# mem.net
KiCad netlist of a schematic drawn in EAGLE
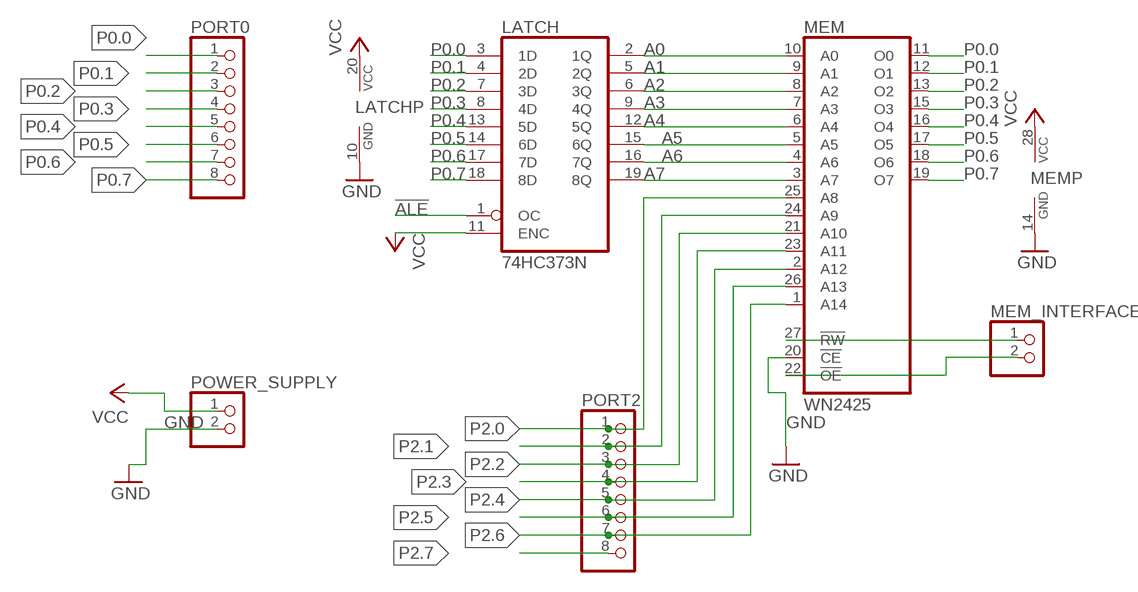
[diagram p0: schematic, sheet 1]

(export (version "E")
  (design (tool "Eeschema 10.0.6"))
  (components
    (comp (ref "LATCH")
      (value "74HC373N")
      (footprint "eagle-import:DIL20")
      (libsource (lib "eagle-import") (part "74373NHC"))
    )
    (comp (ref "MEM")
      (value "WN2425")
      (footprint "eagle-import:DIL28")
      (libsource (lib "eagle-import") (part "TC55257DP"))
    )
    (comp (ref "MEM_INTERFACE")
      (value "PINHD-1X2")
      (footprint "eagle-import:1X02")
      (libsource (lib "eagle-import") (part "PINHD-1X2"))
    )
    (comp (ref "PORT0")
      (value "PINHD-1X8")
      (footprint "eagle-import:1X08")
      (libsource (lib "eagle-import") (part "PINHD-1X8"))
    )
    (comp (ref "PORT2")
      (value "PINHD-1X8")
      (footprint "eagle-import:1X08")
      (libsource (lib "eagle-import") (part "PINHD-1X8"))
    )
    (comp (ref "POWER_SUPPLY")
      (value "PINHD-1X2")
      (footprint "eagle-import:1X02")
      (libsource (lib "eagle-import") (part "PINHD-1X2"))
    )
  )
  (nets
    (net (code "1") (name "/A0") (class "Default")
      (node (ref "LATCH") (pin "2") (pinfunction "1Q_2") (pintype "tri_state"))
      (node (ref "MEM") (pin "10") (pinfunction "A0_10") (pintype "input"))
    )
    (net (code "2") (name "/A1") (class "Default")
      (node (ref "LATCH") (pin "5") (pinfunction "2Q_5") (pintype "tri_state"))
      (node (ref "MEM") (pin "9") (pinfunction "A1_9") (pintype "input"))
    )
    (net (code "3") (name "/A2") (class "Default")
      (node (ref "LATCH") (pin "6") (pinfunction "3Q_6") (pintype "tri_state"))
      (node (ref "MEM") (pin "8") (pinfunction "A2_8") (pintype "input"))
    )
    (net (code "4") (name "/A3") (class "Default")
      (node (ref "LATCH") (pin "9") (pinfunction "4Q_9") (pintype "tri_state"))
      (node (ref "MEM") (pin "7") (pinfunction "A3_7") (pintype "input"))
    )
    (net (code "5") (name "/A4") (class "Default")
      (node (ref "LATCH") (pin "12") (pinfunction "5Q_12") (pintype "tri_state"))
      (node (ref "MEM") (pin "6") (pinfunction "A4_6") (pintype "input"))
    )
    (net (code "6") (name "/A5") (class "Default")
      (node (ref "LATCH") (pin "15") (pinfunction "6Q_15") (pintype "tri_state"))
      (node (ref "MEM") (pin "5") (pinfunction "A5_5") (pintype "input"))
    )
    (net (code "7") (name "/A6") (class "Default")
      (node (ref "LATCH") (pin "16") (pinfunction "7Q_16") (pintype "tri_state"))
      (node (ref "MEM") (pin "4") (pinfunction "A6_4") (pintype "input"))
    )
    (net (code "8") (name "/A7") (class "Default")
      (node (ref "LATCH") (pin "19") (pinfunction "8Q_19") (pintype "tri_state"))
      (node (ref "MEM") (pin "3") (pinfunction "A7_3") (pintype "input"))
    )
    (net (code "9") (name "/~{ALE}") (class "Default")
      (node (ref "LATCH") (pin "1") (pinfunction "OC_1") (pintype "input"))
    )
    (net (code "10") (name "GND") (class "Default")
      (node (ref "LATCH") (pin "10") (pinfunction "GND_10") (pintype "power_in"))
      (node (ref "MEM") (pin "14") (pinfunction "GND_14") (pintype "power_in"))
      (node (ref "MEM") (pin "20") (pinfunction "~{CE}_20") (pintype "input"))
      (node (ref "POWER_SUPPLY") (pin "2") (pinfunction "2_2") (pintype "passive"))
    )
    (net (code "11") (name "Net-(MEMA-~{OE})") (class "Default")
      (node (ref "MEM") (pin "22") (pinfunction "~{OE}_22") (pintype "input"))
      (node (ref "MEM_INTERFACE") (pin "2") (pinfunction "2_2") (pintype "passive"))
    )
    (net (code "12") (name "Net-(MEMA-~{RW})") (class "Default")
      (node (ref "MEM") (pin "27") (pinfunction "~{RW}_27") (pintype "input"))
      (node (ref "MEM_INTERFACE") (pin "1") (pinfunction "1_1") (pintype "passive"))
    )
    (net (code "13") (name "P0.0") (class "Default")
      (node (ref "LATCH") (pin "3") (pinfunction "1D_3") (pintype "input"))
      (node (ref "MEM") (pin "11") (pinfunction "O0_11") (pintype "tri_state"))
      (node (ref "PORT0") (pin "1") (pinfunction "1_1") (pintype "passive"))
    )
    (net (code "14") (name "P0.1") (class "Default")
      (node (ref "LATCH") (pin "4") (pinfunction "2D_4") (pintype "input"))
      (node (ref "MEM") (pin "12") (pinfunction "O1_12") (pintype "tri_state"))
      (node (ref "PORT0") (pin "2") (pinfunction "2_2") (pintype "passive"))
    )
    (net (code "15") (name "P0.2") (class "Default")
      (node (ref "LATCH") (pin "7") (pinfunction "3D_7") (pintype "input"))
      (node (ref "MEM") (pin "13") (pinfunction "O2_13") (pintype "tri_state"))
      (node (ref "PORT0") (pin "3") (pinfunction "3_3") (pintype "passive"))
    )
    (net (code "16") (name "P0.3") (class "Default")
      (node (ref "LATCH") (pin "8") (pinfunction "4D_8") (pintype "input"))
      (node (ref "MEM") (pin "15") (pinfunction "O3_15") (pintype "tri_state"))
      (node (ref "PORT0") (pin "4") (pinfunction "4_4") (pintype "passive"))
    )
    (net (code "17") (name "P0.4") (class "Default")
      (node (ref "LATCH") (pin "13") (pinfunction "5D_13") (pintype "input"))
      (node (ref "MEM") (pin "16") (pinfunction "O4_16") (pintype "tri_state"))
      (node (ref "PORT0") (pin "5") (pinfunction "5_5") (pintype "passive"))
    )
    (net (code "18") (name "P0.5") (class "Default")
      (node (ref "LATCH") (pin "14") (pinfunction "6D_14") (pintype "input"))
      (node (ref "MEM") (pin "17") (pinfunction "O5_17") (pintype "tri_state"))
      (node (ref "PORT0") (pin "6") (pinfunction "6_6") (pintype "passive"))
    )
    (net (code "19") (name "P0.6") (class "Default")
      (node (ref "LATCH") (pin "17") (pinfunction "7D_17") (pintype "input"))
      (node (ref "MEM") (pin "18") (pinfunction "O6_18") (pintype "tri_state"))
      (node (ref "PORT0") (pin "7") (pinfunction "7_7") (pintype "passive"))
    )
    (net (code "20") (name "P0.7") (class "Default")
      (node (ref "LATCH") (pin "18") (pinfunction "8D_18") (pintype "input"))
      (node (ref "MEM") (pin "19") (pinfunction "O7_19") (pintype "tri_state"))
      (node (ref "PORT0") (pin "8") (pinfunction "8_8") (pintype "passive"))
    )
    (net (code "21") (name "P2.0") (class "Default")
      (node (ref "MEM") (pin "25") (pinfunction "A8_25") (pintype "input"))
      (node (ref "PORT2") (pin "1") (pinfunction "1_1") (pintype "passive"))
    )
    (net (code "22") (name "P2.1") (class "Default")
      (node (ref "MEM") (pin "24") (pinfunction "A9_24") (pintype "input"))
      (node (ref "PORT2") (pin "2") (pinfunction "2_2") (pintype "passive"))
    )
    (net (code "23") (name "P2.2") (class "Default")
      (node (ref "MEM") (pin "21") (pinfunction "A10_21") (pintype "input"))
      (node (ref "PORT2") (pin "3") (pinfunction "3_3") (pintype "passive"))
    )
    (net (code "24") (name "P2.3") (class "Default")
      (node (ref "MEM") (pin "23") (pinfunction "A11_23") (pintype "input"))
      (node (ref "PORT2") (pin "4") (pinfunction "4_4") (pintype "passive"))
    )
    (net (code "25") (name "P2.4") (class "Default")
      (node (ref "MEM") (pin "2") (pinfunction "A12_2") (pintype "input"))
      (node (ref "PORT2") (pin "5") (pinfunction "5_5") (pintype "passive"))
    )
    (net (code "26") (name "P2.5") (class "Default")
      (node (ref "MEM") (pin "26") (pinfunction "A13_26") (pintype "input"))
      (node (ref "PORT2") (pin "6") (pinfunction "6_6") (pintype "passive"))
    )
    (net (code "27") (name "P2.6") (class "Default")
      (node (ref "MEM") (pin "1") (pinfunction "A14_1") (pintype "input"))
      (node (ref "PORT2") (pin "7") (pinfunction "7_7") (pintype "passive"))
    )
    (net (code "28") (name "P2.7") (class "Default")
      (node (ref "PORT2") (pin "8") (pinfunction "8_8") (pintype "passive"))
    )
    (net (code "29") (name "VCC") (class "Default")
      (node (ref "LATCH") (pin "11") (pinfunction "ENC_11") (pintype "input"))
      (node (ref "LATCH") (pin "20") (pinfunction "VCC_20") (pintype "power_in"))
      (node (ref "MEM") (pin "28") (pinfunction "VCC_28") (pintype "power_in"))
      (node (ref "POWER_SUPPLY") (pin "1") (pinfunction "1_1") (pintype "passive"))
    )
  )
)
